# me433_2019.net
KiCad netlist of a schematic drawn in EAGLE
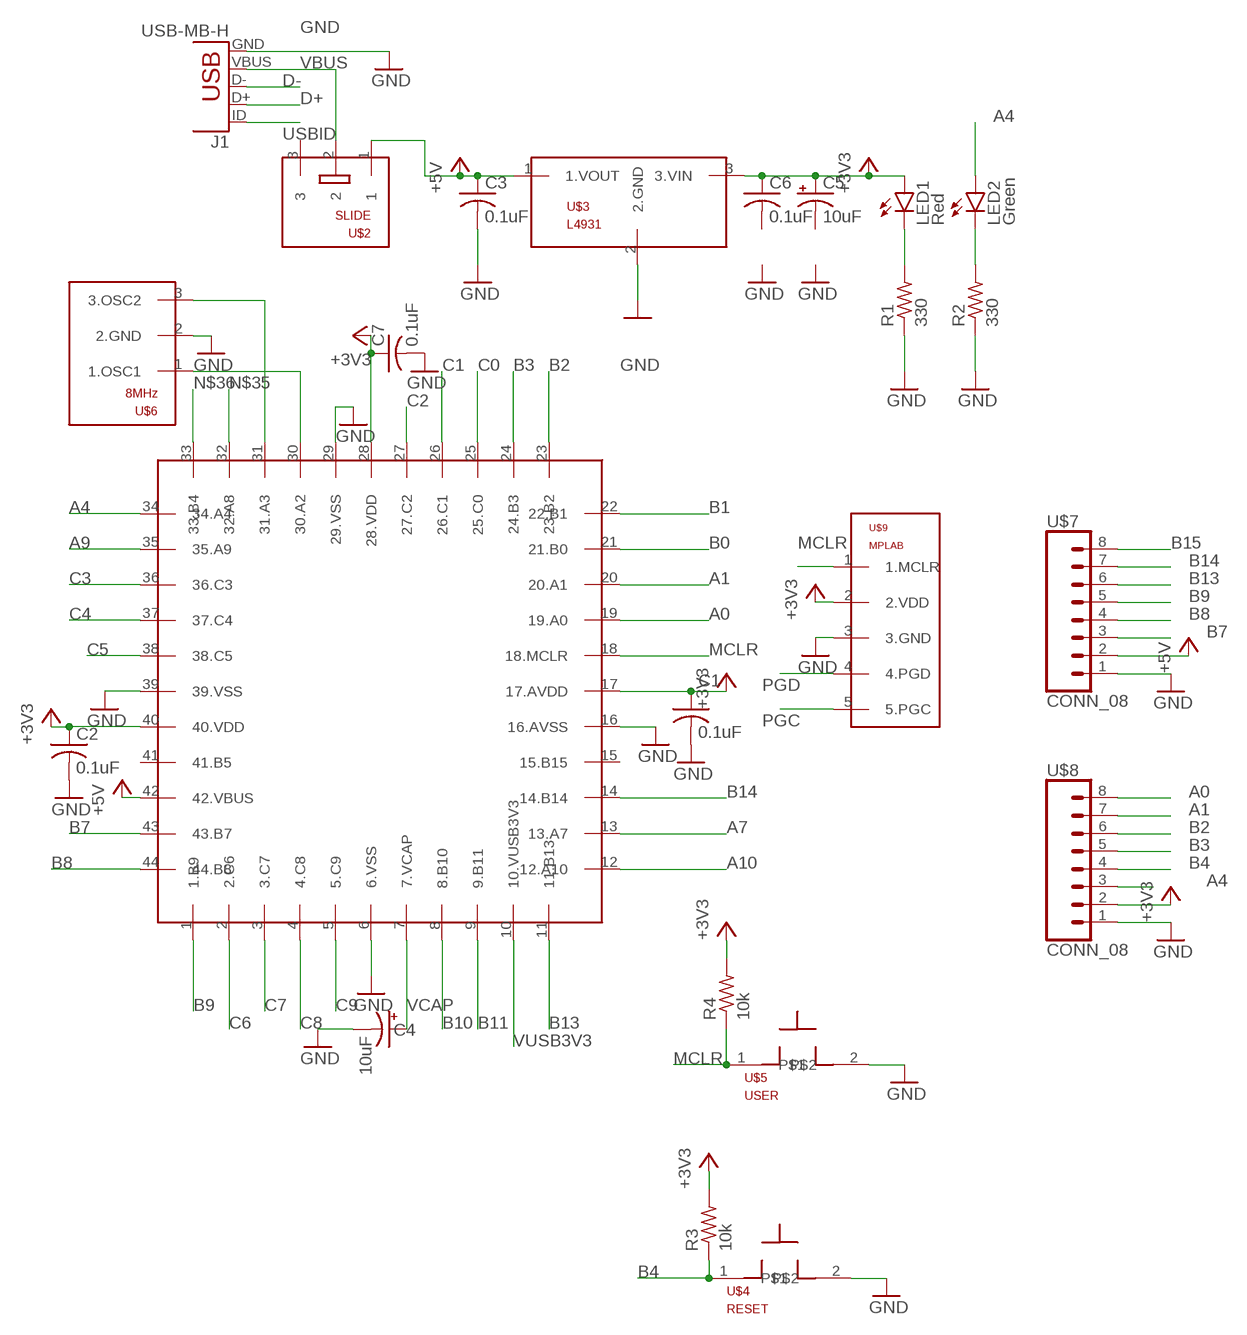
[diagram p0: schematic, sheet 1]

(export (version "E")
  (design (tool "Eeschema 10.0.6"))
  (components
    (comp (ref "C1")
      (value "0.1uF")
      (footprint "eagle-import:C025-025X050")
      (libsource (lib "eagle-import") (part "resistor_348_C-US025-025X050"))
    )
    (comp (ref "C2")
      (value "0.1uF")
      (footprint "eagle-import:C025-025X050")
      (libsource (lib "eagle-import") (part "C-US025-025X050"))
    )
    (comp (ref "C3")
      (value "0.1uF")
      (footprint "eagle-import:C025-025X050")
      (libsource (lib "eagle-import") (part "C-US025-025X050"))
    )
    (comp (ref "C4")
      (value "10uF")
      (footprint "eagle-import:B45181B")
      (libsource (lib "eagle-import") (part "CPOL-USB45181B"))
    )
    (comp (ref "C5")
      (value "10uF")
      (footprint "eagle-import:B45181B")
      (libsource (lib "eagle-import") (part "CPOL-USB45181B"))
    )
    (comp (ref "C6")
      (value "0.1uF")
      (footprint "eagle-import:C025-025X050")
      (libsource (lib "eagle-import") (part "resistor_348_C-US025-025X050"))
    )
    (comp (ref "C7")
      (value "0.1uF")
      (footprint "eagle-import:C025-025X050")
      (libsource (lib "eagle-import") (part "C-US025-025X050"))
    )
    (comp (ref "J1")
      (value "USB-MB-H")
      (footprint "eagle-import:USB-MB-H")
      (libsource (lib "eagle-import") (part "USB-MB-H"))
    )
    (comp (ref "LED1")
      (value "Red")
      (footprint "eagle-import:LED3MM")
      (libsource (lib "eagle-import") (part "LED3MM"))
    )
    (comp (ref "LED2")
      (value "Green")
      (footprint "eagle-import:LED3MM")
      (libsource (lib "eagle-import") (part "LED3MM"))
    )
    (comp (ref "R1")
      (value "330")
      (footprint "eagle-import:0207_10")
      (libsource (lib "eagle-import") (part "R-US_0207/10"))
    )
    (comp (ref "R2")
      (value "330")
      (footprint "eagle-import:0207_10")
      (libsource (lib "eagle-import") (part "R-US_0207/10"))
    )
    (comp (ref "R3")
      (value "10k")
      (footprint "eagle-import:0207_10")
      (libsource (lib "eagle-import") (part "R-US_0207/10"))
    )
    (comp (ref "R4")
      (value "10k")
      (footprint "eagle-import:0207_10")
      (libsource (lib "eagle-import") (part "R-US_0207/10"))
    )
    (comp (ref "U$1")
      (value "PIC32MX270F256D")
      (footprint "eagle-import:TQFP44")
      (libsource (lib "eagle-import") (part "PIC32MX270F256D"))
    )
    (comp (ref "U$2")
      (value "SLIDE")
      (footprint "eagle-import:SLIDE")
      (libsource (lib "eagle-import") (part "SLIDE"))
    )
    (comp (ref "U$3")
      (value "L4931")
      (footprint "eagle-import:TO92")
      (libsource (lib "eagle-import") (part "L4931"))
    )
    (comp (ref "U$4")
      (value "RESET")
      (footprint "eagle-import:PB")
      (libsource (lib "eagle-import") (part "PB"))
    )
    (comp (ref "U$5")
      (value "USER")
      (footprint "eagle-import:PB")
      (libsource (lib "eagle-import") (part "PB"))
    )
    (comp (ref "U$6")
      (value "8MHz")
      (footprint "eagle-import:OSC")
      (libsource (lib "eagle-import") (part "OSC"))
    )
    (comp (ref "U$7")
      (value "CONN_08")
      (footprint "eagle-import:1X08")
      (libsource (lib "eagle-import") (part "CONN_08"))
    )
    (comp (ref "U$8")
      (value "CONN_08")
      (footprint "eagle-import:1X08")
      (libsource (lib "eagle-import") (part "CONN_08"))
    )
    (comp (ref "U$9")
      (value "MPLAB")
      (footprint "eagle-import:1X05")
      (libsource (lib "eagle-import") (part "MPLAB"))
    )
  )
  (nets
    (net (code "1") (name "+3V3") (class "Default")
      (node (ref "C1") (pin "1") (pinfunction "1_1") (pintype "passive"))
      (node (ref "C2") (pin "1") (pinfunction "1_1") (pintype "passive"))
      (node (ref "C5") (pin "+") (pinfunction "+_+") (pintype "passive"))
      (node (ref "C6") (pin "1") (pinfunction "1_1") (pintype "passive"))
      (node (ref "C7") (pin "1") (pinfunction "1_1") (pintype "passive"))
      (node (ref "LED1") (pin "A") (pinfunction "A_A") (pintype "passive"))
      (node (ref "R3") (pin "2") (pinfunction "2_2") (pintype "passive"))
      (node (ref "R4") (pin "2") (pinfunction "2_2") (pintype "passive"))
      (node (ref "U$1") (pin "17") (pinfunction "17.AVDD_17") (pintype "bidirectional"))
      (node (ref "U$1") (pin "28") (pinfunction "28.VDD_28") (pintype "bidirectional"))
      (node (ref "U$1") (pin "40") (pinfunction "40.VDD_40") (pintype "bidirectional"))
      (node (ref "U$3") (pin "3") (pinfunction "3.VIN_3") (pintype "bidirectional"))
      (node (ref "U$8") (pin "2") (pinfunction "2_2") (pintype "passive"))
      (node (ref "U$9") (pin "2") (pinfunction "2.VDD_2") (pintype "bidirectional"))
    )
    (net (code "2") (name "+5V") (class "Default")
      (node (ref "C3") (pin "1") (pinfunction "1_1") (pintype "passive"))
      (node (ref "U$1") (pin "42") (pinfunction "42.VBUS_42") (pintype "bidirectional"))
      (node (ref "U$2") (pin "1") (pinfunction "1_1") (pintype "bidirectional"))
      (node (ref "U$3") (pin "1") (pinfunction "1.VOUT_1") (pintype "bidirectional"))
      (node (ref "U$7") (pin "2") (pinfunction "2_2") (pintype "passive"))
    )
    (net (code "3") (name "/A0") (class "Default")
      (node (ref "U$1") (pin "19") (pinfunction "19.A0_19") (pintype "bidirectional"))
      (node (ref "U$8") (pin "8") (pinfunction "8_8") (pintype "passive"))
    )
    (net (code "4") (name "/A1") (class "Default")
      (node (ref "U$1") (pin "20") (pinfunction "20.A1_20") (pintype "bidirectional"))
      (node (ref "U$8") (pin "7") (pinfunction "7_7") (pintype "passive"))
    )
    (net (code "5") (name "/A4") (class "Default")
      (node (ref "LED2") (pin "A") (pinfunction "A_A") (pintype "passive"))
      (node (ref "U$1") (pin "34") (pinfunction "34.A4_34") (pintype "bidirectional"))
      (node (ref "U$8") (pin "3") (pinfunction "3_3") (pintype "passive"))
    )
    (net (code "6") (name "/A7") (class "Default")
      (node (ref "U$1") (pin "13") (pinfunction "13.A7_13") (pintype "bidirectional"))
    )
    (net (code "7") (name "/A9") (class "Default")
      (node (ref "U$1") (pin "35") (pinfunction "35.A9_35") (pintype "bidirectional"))
    )
    (net (code "8") (name "/A10") (class "Default")
      (node (ref "U$1") (pin "12") (pinfunction "12.A10_12") (pintype "bidirectional"))
    )
    (net (code "9") (name "/B0") (class "Default")
      (node (ref "U$1") (pin "21") (pinfunction "21.B0_21") (pintype "bidirectional"))
    )
    (net (code "10") (name "/B1") (class "Default")
      (node (ref "U$1") (pin "22") (pinfunction "22.B1_22") (pintype "bidirectional"))
    )
    (net (code "11") (name "/B2") (class "Default")
      (node (ref "U$1") (pin "23") (pinfunction "23.B2_23") (pintype "bidirectional"))
      (node (ref "U$8") (pin "6") (pinfunction "6_6") (pintype "passive"))
    )
    (net (code "12") (name "/B3") (class "Default")
      (node (ref "U$1") (pin "24") (pinfunction "24.B3_24") (pintype "bidirectional"))
      (node (ref "U$8") (pin "5") (pinfunction "5_5") (pintype "passive"))
    )
    (net (code "13") (name "/B4") (class "Default")
      (node (ref "R3") (pin "1") (pinfunction "1_1") (pintype "passive"))
      (node (ref "U$4") (pin "1") (pinfunction "P$1_1") (pintype "bidirectional"))
      (node (ref "U$8") (pin "4") (pinfunction "4_4") (pintype "passive"))
    )
    (net (code "14") (name "/B7") (class "Default")
      (node (ref "U$1") (pin "43") (pinfunction "43.B7_43") (pintype "bidirectional"))
      (node (ref "U$7") (pin "3") (pinfunction "3_3") (pintype "passive"))
    )
    (net (code "15") (name "/B8") (class "Default")
      (node (ref "U$1") (pin "44") (pinfunction "44.B8_44") (pintype "bidirectional"))
      (node (ref "U$7") (pin "4") (pinfunction "4_4") (pintype "passive"))
    )
    (net (code "16") (name "/B9") (class "Default")
      (node (ref "U$1") (pin "1") (pinfunction "1.B9_1") (pintype "bidirectional"))
      (node (ref "U$7") (pin "5") (pinfunction "5_5") (pintype "passive"))
    )
    (net (code "17") (name "/B10") (class "Default")
      (node (ref "U$1") (pin "8") (pinfunction "8.B10_8") (pintype "bidirectional"))
    )
    (net (code "18") (name "/B11") (class "Default")
      (node (ref "U$1") (pin "9") (pinfunction "9.B11_9") (pintype "bidirectional"))
    )
    (net (code "19") (name "/B13") (class "Default")
      (node (ref "U$1") (pin "11") (pinfunction "11.B13_11") (pintype "bidirectional"))
      (node (ref "U$7") (pin "6") (pinfunction "6_6") (pintype "passive"))
    )
    (net (code "20") (name "/B14") (class "Default")
      (node (ref "U$1") (pin "14") (pinfunction "14.B14_14") (pintype "bidirectional"))
      (node (ref "U$7") (pin "7") (pinfunction "7_7") (pintype "passive"))
    )
    (net (code "21") (name "/B15") (class "Default")
      (node (ref "U$7") (pin "8") (pinfunction "8_8") (pintype "passive"))
    )
    (net (code "22") (name "/C0") (class "Default")
      (node (ref "U$1") (pin "25") (pinfunction "25.C0_25") (pintype "bidirectional"))
    )
    (net (code "23") (name "/C1") (class "Default")
      (node (ref "U$1") (pin "26") (pinfunction "26.C1_26") (pintype "bidirectional"))
    )
    (net (code "24") (name "/C2") (class "Default")
      (node (ref "U$1") (pin "27") (pinfunction "27.C2_27") (pintype "bidirectional"))
    )
    (net (code "25") (name "/C3") (class "Default")
      (node (ref "U$1") (pin "36") (pinfunction "36.C3_36") (pintype "bidirectional"))
    )
    (net (code "26") (name "/C4") (class "Default")
      (node (ref "U$1") (pin "37") (pinfunction "37.C4_37") (pintype "bidirectional"))
    )
    (net (code "27") (name "/C5") (class "Default")
      (node (ref "U$1") (pin "38") (pinfunction "38.C5_38") (pintype "bidirectional"))
    )
    (net (code "28") (name "/C6") (class "Default")
      (node (ref "U$1") (pin "2") (pinfunction "2.C6_2") (pintype "bidirectional"))
    )
    (net (code "29") (name "/C7") (class "Default")
      (node (ref "U$1") (pin "3") (pinfunction "3.C7_3") (pintype "bidirectional"))
    )
    (net (code "30") (name "/C8") (class "Default")
      (node (ref "U$1") (pin "4") (pinfunction "4.C8_4") (pintype "bidirectional"))
    )
    (net (code "31") (name "/C9") (class "Default")
      (node (ref "U$1") (pin "5") (pinfunction "5.C9_5") (pintype "bidirectional"))
    )
    (net (code "32") (name "/D+") (class "Default")
      (node (ref "J1") (pin "D+") (pinfunction "D-_D+") (pintype "bidirectional"))
    )
    (net (code "33") (name "/D-") (class "Default")
      (node (ref "J1") (pin "D-") (pinfunction "VBUS_D-") (pintype "bidirectional"))
    )
    (net (code "34") (name "/MCLR") (class "Default")
      (node (ref "R4") (pin "1") (pinfunction "1_1") (pintype "passive"))
      (node (ref "U$1") (pin "18") (pinfunction "18.MCLR_18") (pintype "bidirectional"))
      (node (ref "U$5") (pin "1") (pinfunction "P$1_1") (pintype "bidirectional"))
      (node (ref "U$9") (pin "1") (pinfunction "1.MCLR_1") (pintype "bidirectional"))
    )
    (net (code "35") (name "/N$35") (class "Default")
      (node (ref "U$1") (pin "32") (pinfunction "32.A8_32") (pintype "bidirectional"))
    )
    (net (code "36") (name "/N$36") (class "Default")
      (node (ref "U$1") (pin "33") (pinfunction "33.B4_33") (pintype "bidirectional"))
    )
    (net (code "37") (name "/PGC") (class "Default")
      (node (ref "U$9") (pin "5") (pinfunction "5.PGC_5") (pintype "bidirectional"))
    )
    (net (code "38") (name "/PGD") (class "Default")
      (node (ref "U$9") (pin "4") (pinfunction "4.PGD_4") (pintype "bidirectional"))
    )
    (net (code "39") (name "/USBID") (class "Default")
      (node (ref "J1") (pin "ID") (pinfunction "D+_ID") (pintype "bidirectional"))
    )
    (net (code "40") (name "/VBUS") (class "Default")
      (node (ref "J1") (pin "VBUS") (pinfunction "GND_VBUS") (pintype "bidirectional"))
      (node (ref "U$2") (pin "2") (pinfunction "2_2") (pintype "bidirectional"))
    )
    (net (code "41") (name "/VCAP") (class "Default")
      (node (ref "C4") (pin "+") (pinfunction "+_+") (pintype "passive"))
      (node (ref "U$1") (pin "7") (pinfunction "7.VCAP_7") (pintype "bidirectional"))
    )
    (net (code "42") (name "/VUSB3V3") (class "Default")
      (node (ref "U$1") (pin "10") (pinfunction "10.VUSB3V3_10") (pintype "bidirectional"))
    )
    (net (code "43") (name "GND") (class "Default")
      (node (ref "C1") (pin "2") (pinfunction "2_2") (pintype "passive"))
      (node (ref "C2") (pin "2") (pinfunction "2_2") (pintype "passive"))
      (node (ref "C3") (pin "2") (pinfunction "2_2") (pintype "passive"))
      (node (ref "C4") (pin "-") (pinfunction "-_-") (pintype "passive"))
      (node (ref "C7") (pin "2") (pinfunction "2_2") (pintype "passive"))
      (node (ref "J1") (pin "GND") (pinfunction "ID_GND") (pintype "bidirectional"))
      (node (ref "R1") (pin "1") (pinfunction "1_1") (pintype "passive"))
      (node (ref "R2") (pin "1") (pinfunction "1_1") (pintype "passive"))
      (node (ref "U$1") (pin "16") (pinfunction "16.AVSS_16") (pintype "bidirectional"))
      (node (ref "U$1") (pin "29") (pinfunction "29.VSS_29") (pintype "bidirectional"))
      (node (ref "U$1") (pin "39") (pinfunction "39.VSS_39") (pintype "bidirectional"))
      (node (ref "U$1") (pin "6") (pinfunction "6.VSS_6") (pintype "bidirectional"))
      (node (ref "U$3") (pin "2") (pinfunction "2.GND_2") (pintype "bidirectional"))
      (node (ref "U$4") (pin "2") (pinfunction "P$2_2") (pintype "bidirectional"))
      (node (ref "U$5") (pin "2") (pinfunction "P$2_2") (pintype "bidirectional"))
      (node (ref "U$6") (pin "2") (pinfunction "2.GND_2") (pintype "bidirectional"))
      (node (ref "U$7") (pin "1") (pinfunction "1_1") (pintype "passive"))
      (node (ref "U$8") (pin "1") (pinfunction "1_1") (pintype "passive"))
      (node (ref "U$9") (pin "3") (pinfunction "3.GND_3") (pintype "bidirectional"))
    )
    (net (code "44") (name "Net-(LED1-C)") (class "Default")
      (node (ref "LED1") (pin "K") (pinfunction "C_K") (pintype "passive"))
      (node (ref "R1") (pin "2") (pinfunction "2_2") (pintype "passive"))
    )
    (net (code "45") (name "Net-(LED2-C)") (class "Default")
      (node (ref "LED2") (pin "K") (pinfunction "C_K") (pintype "passive"))
      (node (ref "R2") (pin "2") (pinfunction "2_2") (pintype "passive"))
    )
    (net (code "46") (name "Net-(U$1-30.A2)") (class "Default")
      (node (ref "U$1") (pin "30") (pinfunction "30.A2_30") (pintype "bidirectional"))
      (node (ref "U$6") (pin "1") (pinfunction "1.OSC1_1") (pintype "bidirectional"))
    )
    (net (code "47") (name "Net-(U$1-31.A3)") (class "Default")
      (node (ref "U$1") (pin "31") (pinfunction "31.A3_31") (pintype "bidirectional"))
      (node (ref "U$6") (pin "3") (pinfunction "3.OSC2_3") (pintype "bidirectional"))
    )
    (net (code "48") (name "unconnected-(C5-Pad-)") (class "Default")
      (node (ref "C5") (pin "-") (pinfunction "-_-") (pintype "passive"))
    )
    (net (code "49") (name "unconnected-(C6-Pad2)") (class "Default")
      (node (ref "C6") (pin "2") (pinfunction "2_2") (pintype "passive"))
    )
    (net (code "50") (name "unconnected-(U$1-15.B15-Pad15)") (class "Default")
      (node (ref "U$1") (pin "15") (pinfunction "15.B15_15") (pintype "bidirectional"))
    )
    (net (code "51") (name "unconnected-(U$1-41.B5-Pad41)") (class "Default")
      (node (ref "U$1") (pin "41") (pinfunction "41.B5_41") (pintype "bidirectional"))
    )
    (net (code "52") (name "unconnected-(U$2-Pad3)") (class "Default")
      (node (ref "U$2") (pin "3") (pinfunction "3_3") (pintype "bidirectional"))
    )
  )
)
